# FadeCandyS.net
KiCad netlist of a schematic drawn in EAGLE
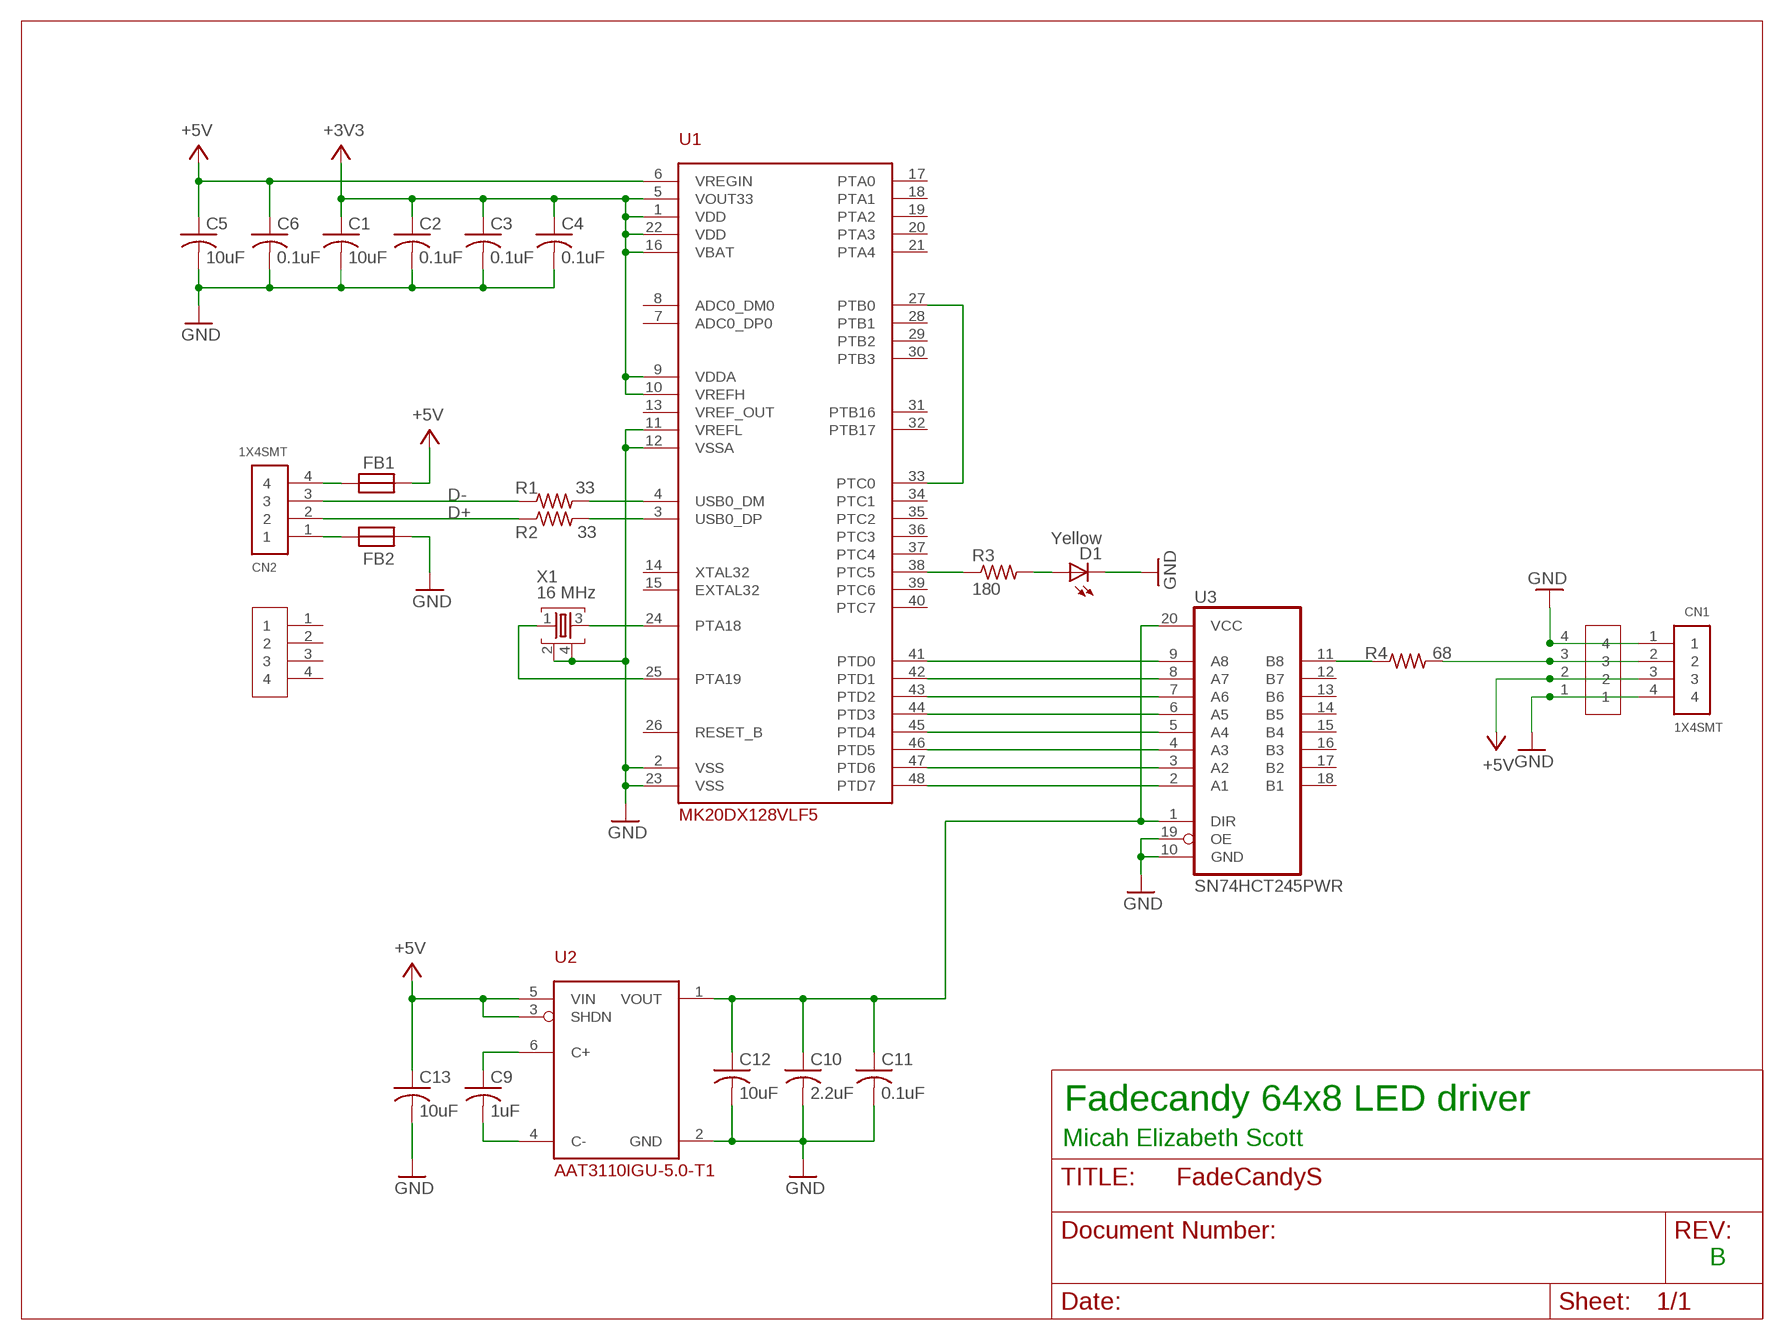
[diagram p0: schematic, sheet 1]

(export (version "E")
  (design (tool "Eeschema 10.0.6"))
  (components
    (comp (ref "1X4_HALFVIA")
      (value "1X4_HALFVIA")
      (footprint "eagle-import:1X4_HALFVIA")
      (libsource (lib "eagle-import") (part "1X4_HALFVIA"))
    )
    (comp (ref "C1")
      (value "10uF")
      (footprint "eagle-import:0805")
      (libsource (lib "eagle-import") (part "C-US0805/NO-OUTLINE"))
    )
    (comp (ref "C2")
      (value "0.1uF")
      (footprint "eagle-import:0805")
      (libsource (lib "eagle-import") (part "C-US0805/NO-OUTLINE"))
    )
    (comp (ref "C3")
      (value "0.1uF")
      (footprint "eagle-import:0805")
      (libsource (lib "eagle-import") (part "C-US0805/NO-OUTLINE"))
    )
    (comp (ref "C4")
      (value "0.1uF")
      (footprint "eagle-import:0805")
      (libsource (lib "eagle-import") (part "C-US0805/NO-OUTLINE"))
    )
    (comp (ref "C5")
      (value "10uF")
      (footprint "eagle-import:0805")
      (libsource (lib "eagle-import") (part "C-US0805/NO-OUTLINE"))
    )
    (comp (ref "C6")
      (value "0.1uF")
      (footprint "eagle-import:0805")
      (libsource (lib "eagle-import") (part "C-US0805/NO-OUTLINE"))
    )
    (comp (ref "C9")
      (value "1uF")
      (footprint "eagle-import:0805")
      (libsource (lib "eagle-import") (part "C-US0805/NO-OUTLINE"))
    )
    (comp (ref "C10")
      (value "2.2uF")
      (footprint "eagle-import:0805")
      (libsource (lib "eagle-import") (part "C-US0805/NO-OUTLINE"))
    )
    (comp (ref "C11")
      (value "0.1uF")
      (footprint "eagle-import:0805")
      (libsource (lib "eagle-import") (part "C-US0805/NO-OUTLINE"))
    )
    (comp (ref "C12")
      (value "10uF")
      (footprint "eagle-import:0805")
      (libsource (lib "eagle-import") (part "C-US0805/NO-OUTLINE"))
    )
    (comp (ref "C13")
      (value "10uF")
      (footprint "eagle-import:0805")
      (libsource (lib "eagle-import") (part "C-US0805/NO-OUTLINE"))
    )
    (comp (ref "CN1")
      (value "1X4SMT")
      (footprint "eagle-import:1X4-SMT")
      (libsource (lib "eagle-import") (part "1X4SMT"))
    )
    (comp (ref "CN2")
      (value "1X4SMT")
      (footprint "eagle-import:1X4-SMT")
      (libsource (lib "eagle-import") (part "1X4SMT"))
    )
    (comp (ref "D1")
      (value "Yellow")
      (footprint "eagle-import:CHIP-LED0805")
      (libsource (lib "eagle-import") (part "LEDCHIP-LED0805"))
    )
    (comp (ref "FB1")
      (value "FB0805/NO-OUTLINE")
      (footprint "eagle-import:0805")
      (libsource (lib "eagle-import") (part "FB0805/NO-OUTLINE"))
    )
    (comp (ref "FB2")
      (value "FB0805/NO-OUTLINE")
      (footprint "eagle-import:0805")
      (libsource (lib "eagle-import") (part "FB0805/NO-OUTLINE"))
    )
    (comp (ref "R1")
      (value "33")
      (footprint "eagle-import:0805")
      (libsource (lib "eagle-import") (part "R-US_0805/NO-OUTLINE"))
    )
    (comp (ref "R2")
      (value "33")
      (footprint "eagle-import:0805")
      (libsource (lib "eagle-import") (part "R-US_0805/NO-OUTLINE"))
    )
    (comp (ref "R3")
      (value "180")
      (footprint "eagle-import:0805")
      (libsource (lib "eagle-import") (part "R-US_0805/NO-OUTLINE"))
    )
    (comp (ref "R4")
      (value "68")
      (footprint "eagle-import:0805")
      (libsource (lib "eagle-import") (part "R-US_0805/NO-OUTLINE"))
    )
    (comp (ref "U$1")
      (value "1X4_HALFVIA")
      (footprint "eagle-import:1X4_HALFVIA")
      (libsource (lib "eagle-import") (part "1X4_HALFVIA"))
    )
    (comp (ref "U1")
      (value "MK20DX128VLF5")
      (footprint "eagle-import:LQFP48")
      (libsource (lib "eagle-import") (part "MK20DX128VLF5"))
    )
    (comp (ref "U2")
      (value "AAT3110IGU-5.0-T1")
      (footprint "eagle-import:SOT23-6L")
      (libsource (lib "eagle-import") (part "AAT3110"))
    )
    (comp (ref "U3")
      (value "SN74HCT245PWR")
      (footprint "eagle-import:TSSOP20")
      (libsource (lib "eagle-import") (part "74245PW"))
    )
    (comp (ref "X1")
      (value "16 MHz")
      (footprint "eagle-import:TSX-3225")
      (libsource (lib "eagle-import") (part "TSX-32250"))
    )
  )
  (nets
    (net (code "1") (name "+3V3") (class "Default")
      (node (ref "C1") (pin "1") (pinfunction "1_1") (pintype "passive"))
      (node (ref "C2") (pin "1") (pinfunction "1_1") (pintype "passive"))
      (node (ref "C3") (pin "1") (pinfunction "1_1") (pintype "passive"))
      (node (ref "C4") (pin "1") (pinfunction "1_1") (pintype "passive"))
      (node (ref "U1") (pin "1") (pinfunction "VDD_1") (pintype "bidirectional"))
      (node (ref "U1") (pin "10") (pinfunction "VREFH_10") (pintype "bidirectional"))
      (node (ref "U1") (pin "16") (pinfunction "VBAT_16") (pintype "bidirectional"))
      (node (ref "U1") (pin "22") (pinfunction "VDD_22") (pintype "bidirectional"))
      (node (ref "U1") (pin "5") (pinfunction "VOUT33_5") (pintype "bidirectional"))
      (node (ref "U1") (pin "9") (pinfunction "VDDA_9") (pintype "bidirectional"))
    )
    (net (code "2") (name "+5V") (class "Default")
      (node (ref "1X4_HALFVIA") (pin "2") (pinfunction "2_2") (pintype "bidirectional"))
      (node (ref "C13") (pin "1") (pinfunction "1_1") (pintype "passive"))
      (node (ref "C5") (pin "1") (pinfunction "1_1") (pintype "passive"))
      (node (ref "C6") (pin "1") (pinfunction "1_1") (pintype "passive"))
      (node (ref "CN1") (pin "3") (pinfunction "3_3") (pintype "bidirectional"))
      (node (ref "FB1") (pin "2") (pinfunction "P$2_2") (pintype "bidirectional"))
      (node (ref "U1") (pin "6") (pinfunction "VREGIN_6") (pintype "bidirectional"))
      (node (ref "U2") (pin "3") (pinfunction "SHDN_3") (pintype "bidirectional"))
      (node (ref "U2") (pin "5") (pinfunction "VIN_5") (pintype "bidirectional"))
    )
    (net (code "3") (name "/D+") (class "Default")
      (node (ref "CN2") (pin "2") (pinfunction "2_2") (pintype "bidirectional"))
      (node (ref "R2") (pin "1") (pinfunction "1_1") (pintype "passive"))
    )
    (net (code "4") (name "/D-") (class "Default")
      (node (ref "CN2") (pin "3") (pinfunction "3_3") (pintype "bidirectional"))
      (node (ref "R1") (pin "1") (pinfunction "1_1") (pintype "passive"))
    )
    (net (code "5") (name "GND") (class "Default")
      (node (ref "1X4_HALFVIA") (pin "1") (pinfunction "1_1") (pintype "bidirectional"))
      (node (ref "1X4_HALFVIA") (pin "4") (pinfunction "4_4") (pintype "bidirectional"))
      (node (ref "C1") (pin "2") (pinfunction "2_2") (pintype "passive"))
      (node (ref "C10") (pin "2") (pinfunction "2_2") (pintype "passive"))
      (node (ref "C11") (pin "2") (pinfunction "2_2") (pintype "passive"))
      (node (ref "C12") (pin "2") (pinfunction "2_2") (pintype "passive"))
      (node (ref "C13") (pin "2") (pinfunction "2_2") (pintype "passive"))
      (node (ref "C2") (pin "2") (pinfunction "2_2") (pintype "passive"))
      (node (ref "C3") (pin "2") (pinfunction "2_2") (pintype "passive"))
      (node (ref "C4") (pin "2") (pinfunction "2_2") (pintype "passive"))
      (node (ref "C5") (pin "2") (pinfunction "2_2") (pintype "passive"))
      (node (ref "C6") (pin "2") (pinfunction "2_2") (pintype "passive"))
      (node (ref "CN1") (pin "1") (pinfunction "1_1") (pintype "bidirectional"))
      (node (ref "CN1") (pin "4") (pinfunction "4_4") (pintype "bidirectional"))
      (node (ref "D1") (pin "C") (pinfunction "C_C") (pintype "passive"))
      (node (ref "FB2") (pin "2") (pinfunction "P$2_2") (pintype "bidirectional"))
      (node (ref "U1") (pin "11") (pinfunction "VREFL_11") (pintype "bidirectional"))
      (node (ref "U1") (pin "12") (pinfunction "VSSA_12") (pintype "bidirectional"))
      (node (ref "U1") (pin "2") (pinfunction "VSS_2") (pintype "bidirectional"))
      (node (ref "U1") (pin "23") (pinfunction "VSS_23") (pintype "bidirectional"))
      (node (ref "U2") (pin "2") (pinfunction "GND_2") (pintype "bidirectional"))
      (node (ref "U3") (pin "10") (pinfunction "GND_10") (pintype "bidirectional"))
      (node (ref "U3") (pin "19") (pinfunction "OE_19") (pintype "input"))
      (node (ref "X1") (pin "2") (pinfunction "2_2") (pintype "passive"))
      (node (ref "X1") (pin "4") (pinfunction "4_4") (pintype "passive"))
    )
    (net (code "6") (name "Net-(1X4_HALFVIA-Pad3)") (class "Default")
      (node (ref "1X4_HALFVIA") (pin "3") (pinfunction "3_3") (pintype "bidirectional"))
      (node (ref "CN1") (pin "2") (pinfunction "2_2") (pintype "bidirectional"))
      (node (ref "R4") (pin "2") (pinfunction "2_2") (pintype "passive"))
    )
    (net (code "7") (name "Net-(D1-PadA)") (class "Default")
      (node (ref "D1") (pin "A") (pinfunction "A_A") (pintype "passive"))
      (node (ref "R3") (pin "2") (pinfunction "2_2") (pintype "passive"))
    )
    (net (code "8") (name "Net-(FB1-P$1)") (class "Default")
      (node (ref "CN2") (pin "4") (pinfunction "4_4") (pintype "bidirectional"))
      (node (ref "FB1") (pin "1") (pinfunction "P$1_1") (pintype "bidirectional"))
    )
    (net (code "9") (name "Net-(FB2-P$1)") (class "Default")
      (node (ref "CN2") (pin "1") (pinfunction "1_1") (pintype "bidirectional"))
      (node (ref "FB2") (pin "1") (pinfunction "P$1_1") (pintype "bidirectional"))
    )
    (net (code "10") (name "Net-(U1-PTA18)") (class "Default")
      (node (ref "U1") (pin "24") (pinfunction "PTA18_24") (pintype "bidirectional"))
      (node (ref "X1") (pin "3") (pinfunction "3_3") (pintype "passive"))
    )
    (net (code "11") (name "Net-(U1-PTA19)") (class "Default")
      (node (ref "U1") (pin "25") (pinfunction "PTA19_25") (pintype "bidirectional"))
      (node (ref "X1") (pin "1") (pinfunction "1_1") (pintype "passive"))
    )
    (net (code "12") (name "Net-(U1-PTB0)") (class "Default")
      (node (ref "U1") (pin "27") (pinfunction "PTB0_27") (pintype "bidirectional"))
      (node (ref "U1") (pin "33") (pinfunction "PTC0_33") (pintype "bidirectional"))
    )
    (net (code "13") (name "Net-(U1-PTC5)") (class "Default")
      (node (ref "R3") (pin "1") (pinfunction "1_1") (pintype "passive"))
      (node (ref "U1") (pin "38") (pinfunction "PTC5_38") (pintype "bidirectional"))
    )
    (net (code "14") (name "Net-(U1-PTD0)") (class "Default")
      (node (ref "U1") (pin "41") (pinfunction "PTD0_41") (pintype "bidirectional"))
      (node (ref "U3") (pin "9") (pinfunction "A8_9") (pintype "bidirectional"))
    )
    (net (code "15") (name "Net-(U1-PTD1)") (class "Default")
      (node (ref "U1") (pin "42") (pinfunction "PTD1_42") (pintype "bidirectional"))
      (node (ref "U3") (pin "8") (pinfunction "A7_8") (pintype "bidirectional"))
    )
    (net (code "16") (name "Net-(U1-PTD2)") (class "Default")
      (node (ref "U1") (pin "43") (pinfunction "PTD2_43") (pintype "bidirectional"))
      (node (ref "U3") (pin "7") (pinfunction "A6_7") (pintype "bidirectional"))
    )
    (net (code "17") (name "Net-(U1-PTD3)") (class "Default")
      (node (ref "U1") (pin "44") (pinfunction "PTD3_44") (pintype "bidirectional"))
      (node (ref "U3") (pin "6") (pinfunction "A5_6") (pintype "bidirectional"))
    )
    (net (code "18") (name "Net-(U1-PTD4)") (class "Default")
      (node (ref "U1") (pin "45") (pinfunction "PTD4_45") (pintype "bidirectional"))
      (node (ref "U3") (pin "5") (pinfunction "A4_5") (pintype "bidirectional"))
    )
    (net (code "19") (name "Net-(U1-PTD5)") (class "Default")
      (node (ref "U1") (pin "46") (pinfunction "PTD5_46") (pintype "bidirectional"))
      (node (ref "U3") (pin "4") (pinfunction "A3_4") (pintype "bidirectional"))
    )
    (net (code "20") (name "Net-(U1-PTD6)") (class "Default")
      (node (ref "U1") (pin "47") (pinfunction "PTD6_47") (pintype "bidirectional"))
      (node (ref "U3") (pin "3") (pinfunction "A2_3") (pintype "bidirectional"))
    )
    (net (code "21") (name "Net-(U1-PTD7)") (class "Default")
      (node (ref "U1") (pin "48") (pinfunction "PTD7_48") (pintype "bidirectional"))
      (node (ref "U3") (pin "2") (pinfunction "A1_2") (pintype "bidirectional"))
    )
    (net (code "22") (name "Net-(U1-USB0_DM)") (class "Default")
      (node (ref "R1") (pin "2") (pinfunction "2_2") (pintype "passive"))
      (node (ref "U1") (pin "4") (pinfunction "USB0_DM_4") (pintype "bidirectional"))
    )
    (net (code "23") (name "Net-(U1-USB0_DP)") (class "Default")
      (node (ref "R2") (pin "2") (pinfunction "2_2") (pintype "passive"))
      (node (ref "U1") (pin "3") (pinfunction "USB0_DP_3") (pintype "bidirectional"))
    )
    (net (code "24") (name "Net-(U2-C+)") (class "Default")
      (node (ref "C9") (pin "1") (pinfunction "1_1") (pintype "passive"))
      (node (ref "U2") (pin "6") (pinfunction "C+_6") (pintype "bidirectional"))
    )
    (net (code "25") (name "Net-(U2-C-)") (class "Default")
      (node (ref "C9") (pin "2") (pinfunction "2_2") (pintype "passive"))
      (node (ref "U2") (pin "4") (pinfunction "C-_4") (pintype "bidirectional"))
    )
    (net (code "26") (name "Net-(U2-VOUT)") (class "Default")
      (node (ref "C10") (pin "1") (pinfunction "1_1") (pintype "passive"))
      (node (ref "C11") (pin "1") (pinfunction "1_1") (pintype "passive"))
      (node (ref "C12") (pin "1") (pinfunction "1_1") (pintype "passive"))
      (node (ref "U2") (pin "1") (pinfunction "VOUT_1") (pintype "bidirectional"))
      (node (ref "U3") (pin "1") (pinfunction "DIR_1") (pintype "input"))
      (node (ref "U3") (pin "20") (pinfunction "VCC_20") (pintype "bidirectional"))
    )
    (net (code "27") (name "Net-(U3-B8)") (class "Default")
      (node (ref "R4") (pin "1") (pinfunction "1_1") (pintype "passive"))
      (node (ref "U3") (pin "11") (pinfunction "B8_11") (pintype "bidirectional"))
    )
    (net (code "28") (name "unconnected-(U$1-Pad1)") (class "Default")
      (node (ref "U$1") (pin "1") (pinfunction "1_1") (pintype "bidirectional"))
    )
    (net (code "29") (name "unconnected-(U$1-Pad2)") (class "Default")
      (node (ref "U$1") (pin "2") (pinfunction "2_2") (pintype "bidirectional"))
    )
    (net (code "30") (name "unconnected-(U$1-Pad3)") (class "Default")
      (node (ref "U$1") (pin "3") (pinfunction "3_3") (pintype "bidirectional"))
    )
    (net (code "31") (name "unconnected-(U$1-Pad4)") (class "Default")
      (node (ref "U$1") (pin "4") (pinfunction "4_4") (pintype "bidirectional"))
    )
    (net (code "32") (name "unconnected-(U1-ADC0_DM0-Pad8)") (class "Default")
      (node (ref "U1") (pin "8") (pinfunction "ADC0_DM0_8") (pintype "bidirectional"))
    )
    (net (code "33") (name "unconnected-(U1-ADC0_DP0-Pad7)") (class "Default")
      (node (ref "U1") (pin "7") (pinfunction "ADC0_DP0_7") (pintype "bidirectional"))
    )
    (net (code "34") (name "unconnected-(U1-EXTAL32-Pad15)") (class "Default")
      (node (ref "U1") (pin "15") (pinfunction "EXTAL32_15") (pintype "bidirectional"))
    )
    (net (code "35") (name "unconnected-(U1-PTA0-Pad17)") (class "Default")
      (node (ref "U1") (pin "17") (pinfunction "PTA0_17") (pintype "bidirectional"))
    )
    (net (code "36") (name "unconnected-(U1-PTA1-Pad18)") (class "Default")
      (node (ref "U1") (pin "18") (pinfunction "PTA1_18") (pintype "bidirectional"))
    )
    (net (code "37") (name "unconnected-(U1-PTA2-Pad19)") (class "Default")
      (node (ref "U1") (pin "19") (pinfunction "PTA2_19") (pintype "bidirectional"))
    )
    (net (code "38") (name "unconnected-(U1-PTA3-Pad20)") (class "Default")
      (node (ref "U1") (pin "20") (pinfunction "PTA3_20") (pintype "bidirectional"))
    )
    (net (code "39") (name "unconnected-(U1-PTA4-Pad21)") (class "Default")
      (node (ref "U1") (pin "21") (pinfunction "PTA4_21") (pintype "bidirectional"))
    )
    (net (code "40") (name "unconnected-(U1-PTB1-Pad28)") (class "Default")
      (node (ref "U1") (pin "28") (pinfunction "PTB1_28") (pintype "bidirectional"))
    )
    (net (code "41") (name "unconnected-(U1-PTB2-Pad29)") (class "Default")
      (node (ref "U1") (pin "29") (pinfunction "PTB2_29") (pintype "bidirectional"))
    )
    (net (code "42") (name "unconnected-(U1-PTB3-Pad30)") (class "Default")
      (node (ref "U1") (pin "30") (pinfunction "PTB3_30") (pintype "bidirectional"))
    )
    (net (code "43") (name "unconnected-(U1-PTB16-Pad31)") (class "Default")
      (node (ref "U1") (pin "31") (pinfunction "PTB16_31") (pintype "bidirectional"))
    )
    (net (code "44") (name "unconnected-(U1-PTB17-Pad32)") (class "Default")
      (node (ref "U1") (pin "32") (pinfunction "PTB17_32") (pintype "bidirectional"))
    )
    (net (code "45") (name "unconnected-(U1-PTC1-Pad34)") (class "Default")
      (node (ref "U1") (pin "34") (pinfunction "PTC1_34") (pintype "bidirectional"))
    )
    (net (code "46") (name "unconnected-(U1-PTC2-Pad35)") (class "Default")
      (node (ref "U1") (pin "35") (pinfunction "PTC2_35") (pintype "bidirectional"))
    )
    (net (code "47") (name "unconnected-(U1-PTC3-Pad36)") (class "Default")
      (node (ref "U1") (pin "36") (pinfunction "PTC3_36") (pintype "bidirectional"))
    )
    (net (code "48") (name "unconnected-(U1-PTC4-Pad37)") (class "Default")
      (node (ref "U1") (pin "37") (pinfunction "PTC4_37") (pintype "bidirectional"))
    )
    (net (code "49") (name "unconnected-(U1-PTC6-Pad39)") (class "Default")
      (node (ref "U1") (pin "39") (pinfunction "PTC6_39") (pintype "bidirectional"))
    )
    (net (code "50") (name "unconnected-(U1-PTC7-Pad40)") (class "Default")
      (node (ref "U1") (pin "40") (pinfunction "PTC7_40") (pintype "bidirectional"))
    )
    (net (code "51") (name "unconnected-(U1-RESET_B-Pad26)") (class "Default")
      (node (ref "U1") (pin "26") (pinfunction "RESET_B_26") (pintype "bidirectional"))
    )
    (net (code "52") (name "unconnected-(U1-VREF_OUT-Pad13)") (class "Default")
      (node (ref "U1") (pin "13") (pinfunction "VREF_OUT_13") (pintype "bidirectional"))
    )
    (net (code "53") (name "unconnected-(U1-XTAL32-Pad14)") (class "Default")
      (node (ref "U1") (pin "14") (pinfunction "XTAL32_14") (pintype "bidirectional"))
    )
    (net (code "54") (name "unconnected-(U3-B1-Pad18)") (class "Default")
      (node (ref "U3") (pin "18") (pinfunction "B1_18") (pintype "bidirectional"))
    )
    (net (code "55") (name "unconnected-(U3-B2-Pad17)") (class "Default")
      (node (ref "U3") (pin "17") (pinfunction "B2_17") (pintype "bidirectional"))
    )
    (net (code "56") (name "unconnected-(U3-B3-Pad16)") (class "Default")
      (node (ref "U3") (pin "16") (pinfunction "B3_16") (pintype "bidirectional"))
    )
    (net (code "57") (name "unconnected-(U3-B4-Pad15)") (class "Default")
      (node (ref "U3") (pin "15") (pinfunction "B4_15") (pintype "bidirectional"))
    )
    (net (code "58") (name "unconnected-(U3-B5-Pad14)") (class "Default")
      (node (ref "U3") (pin "14") (pinfunction "B5_14") (pintype "bidirectional"))
    )
    (net (code "59") (name "unconnected-(U3-B6-Pad13)") (class "Default")
      (node (ref "U3") (pin "13") (pinfunction "B6_13") (pintype "bidirectional"))
    )
    (net (code "60") (name "unconnected-(U3-B7-Pad12)") (class "Default")
      (node (ref "U3") (pin "12") (pinfunction "B7_12") (pintype "bidirectional"))
    )
  )
)
